# SCH.net
KiCad netlist of a schematic drawn in Altium Designer
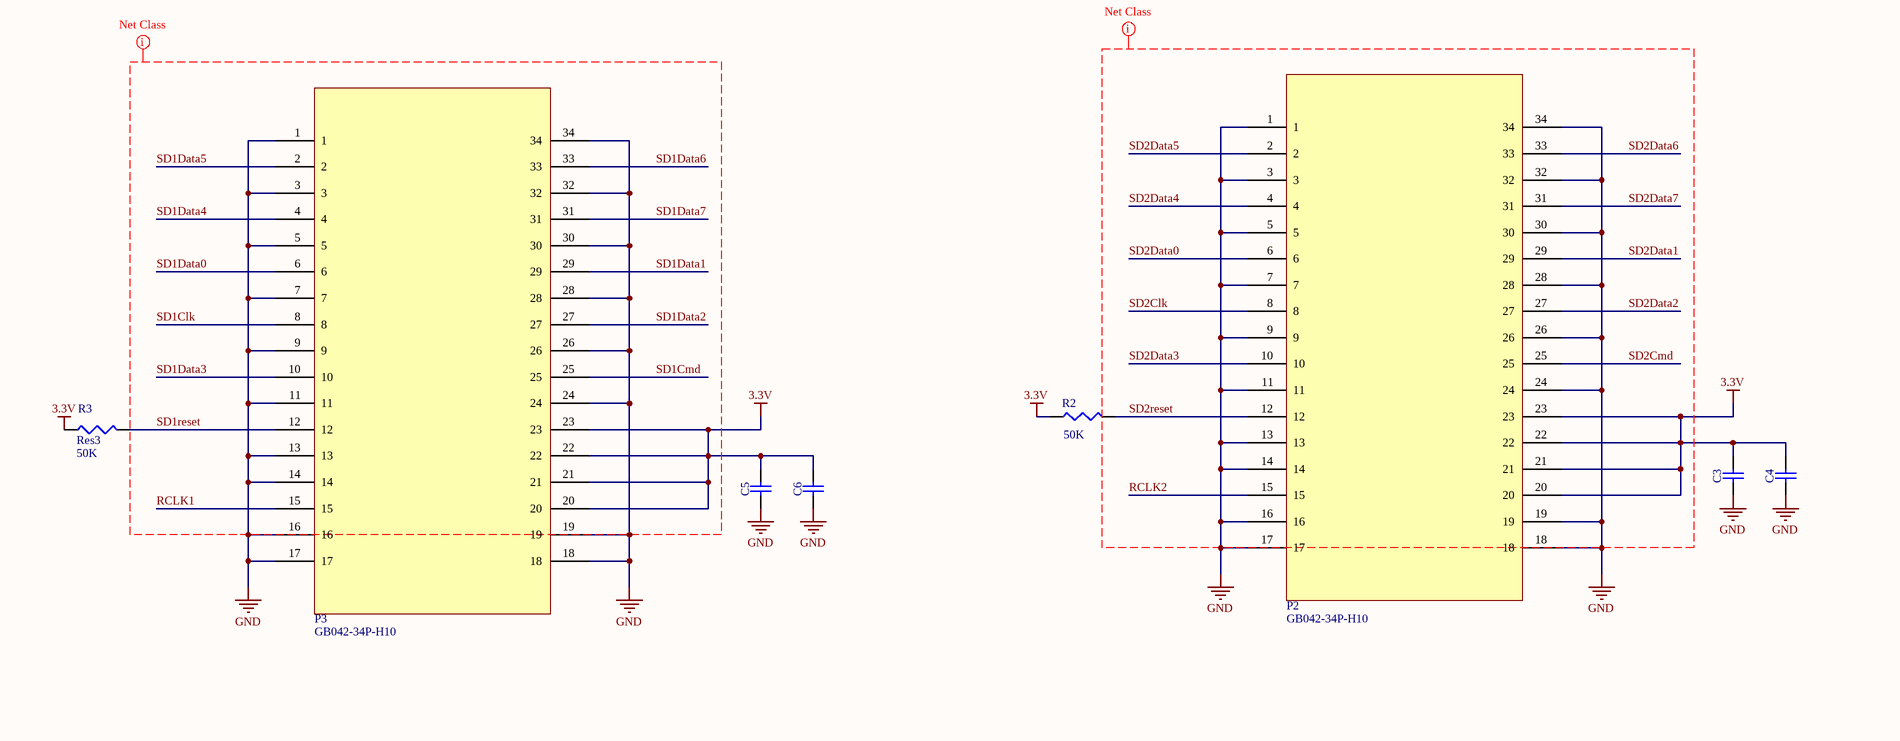
[diagram p0: SCH.SchDoc, top left]
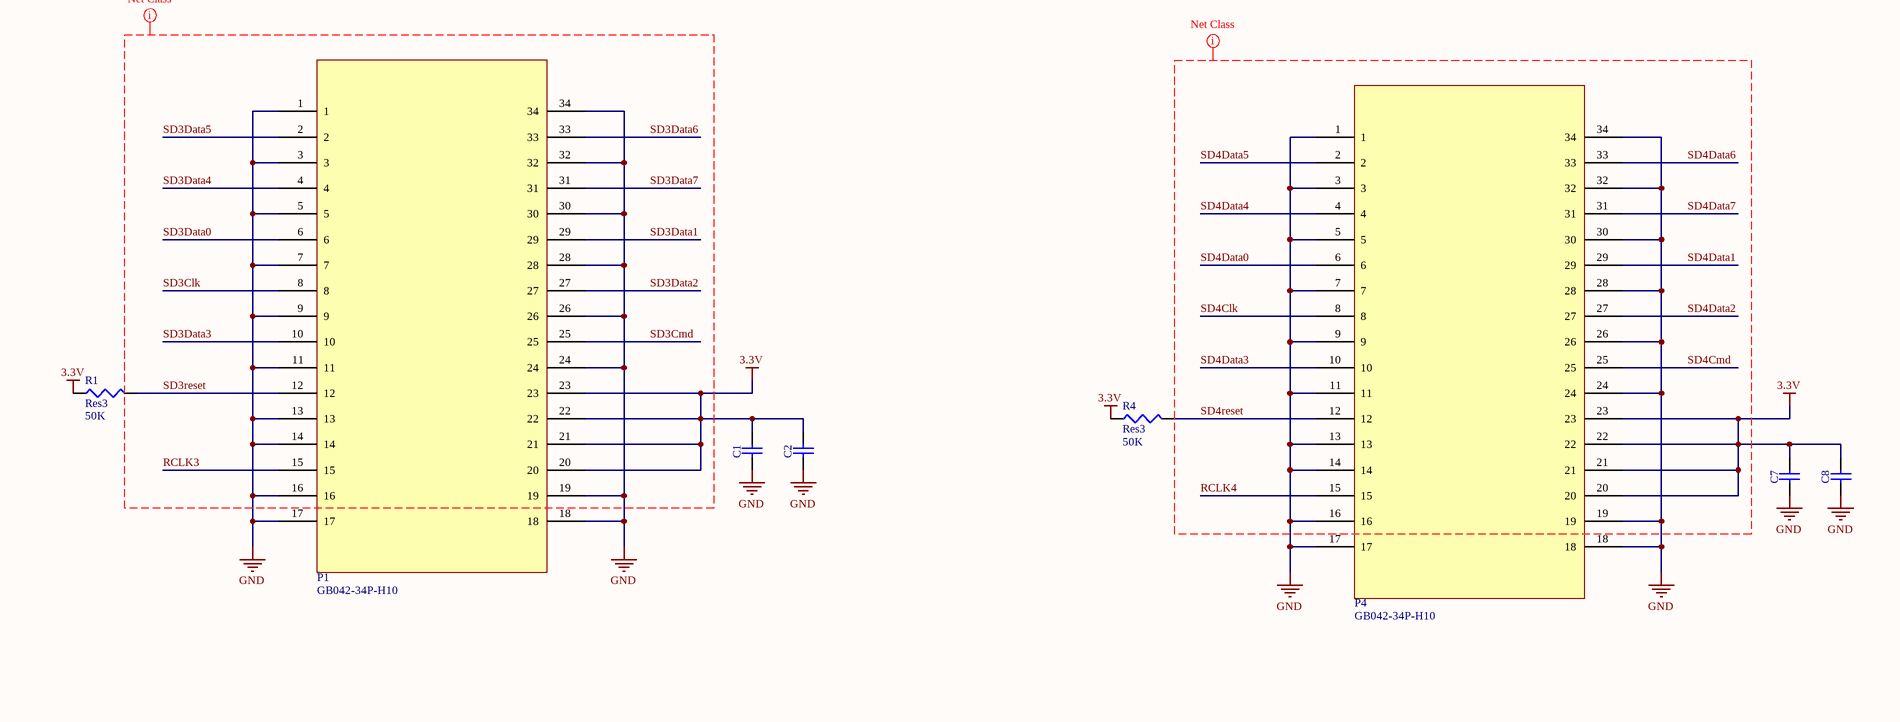
[diagram p1: SCH.SchDoc, top right]
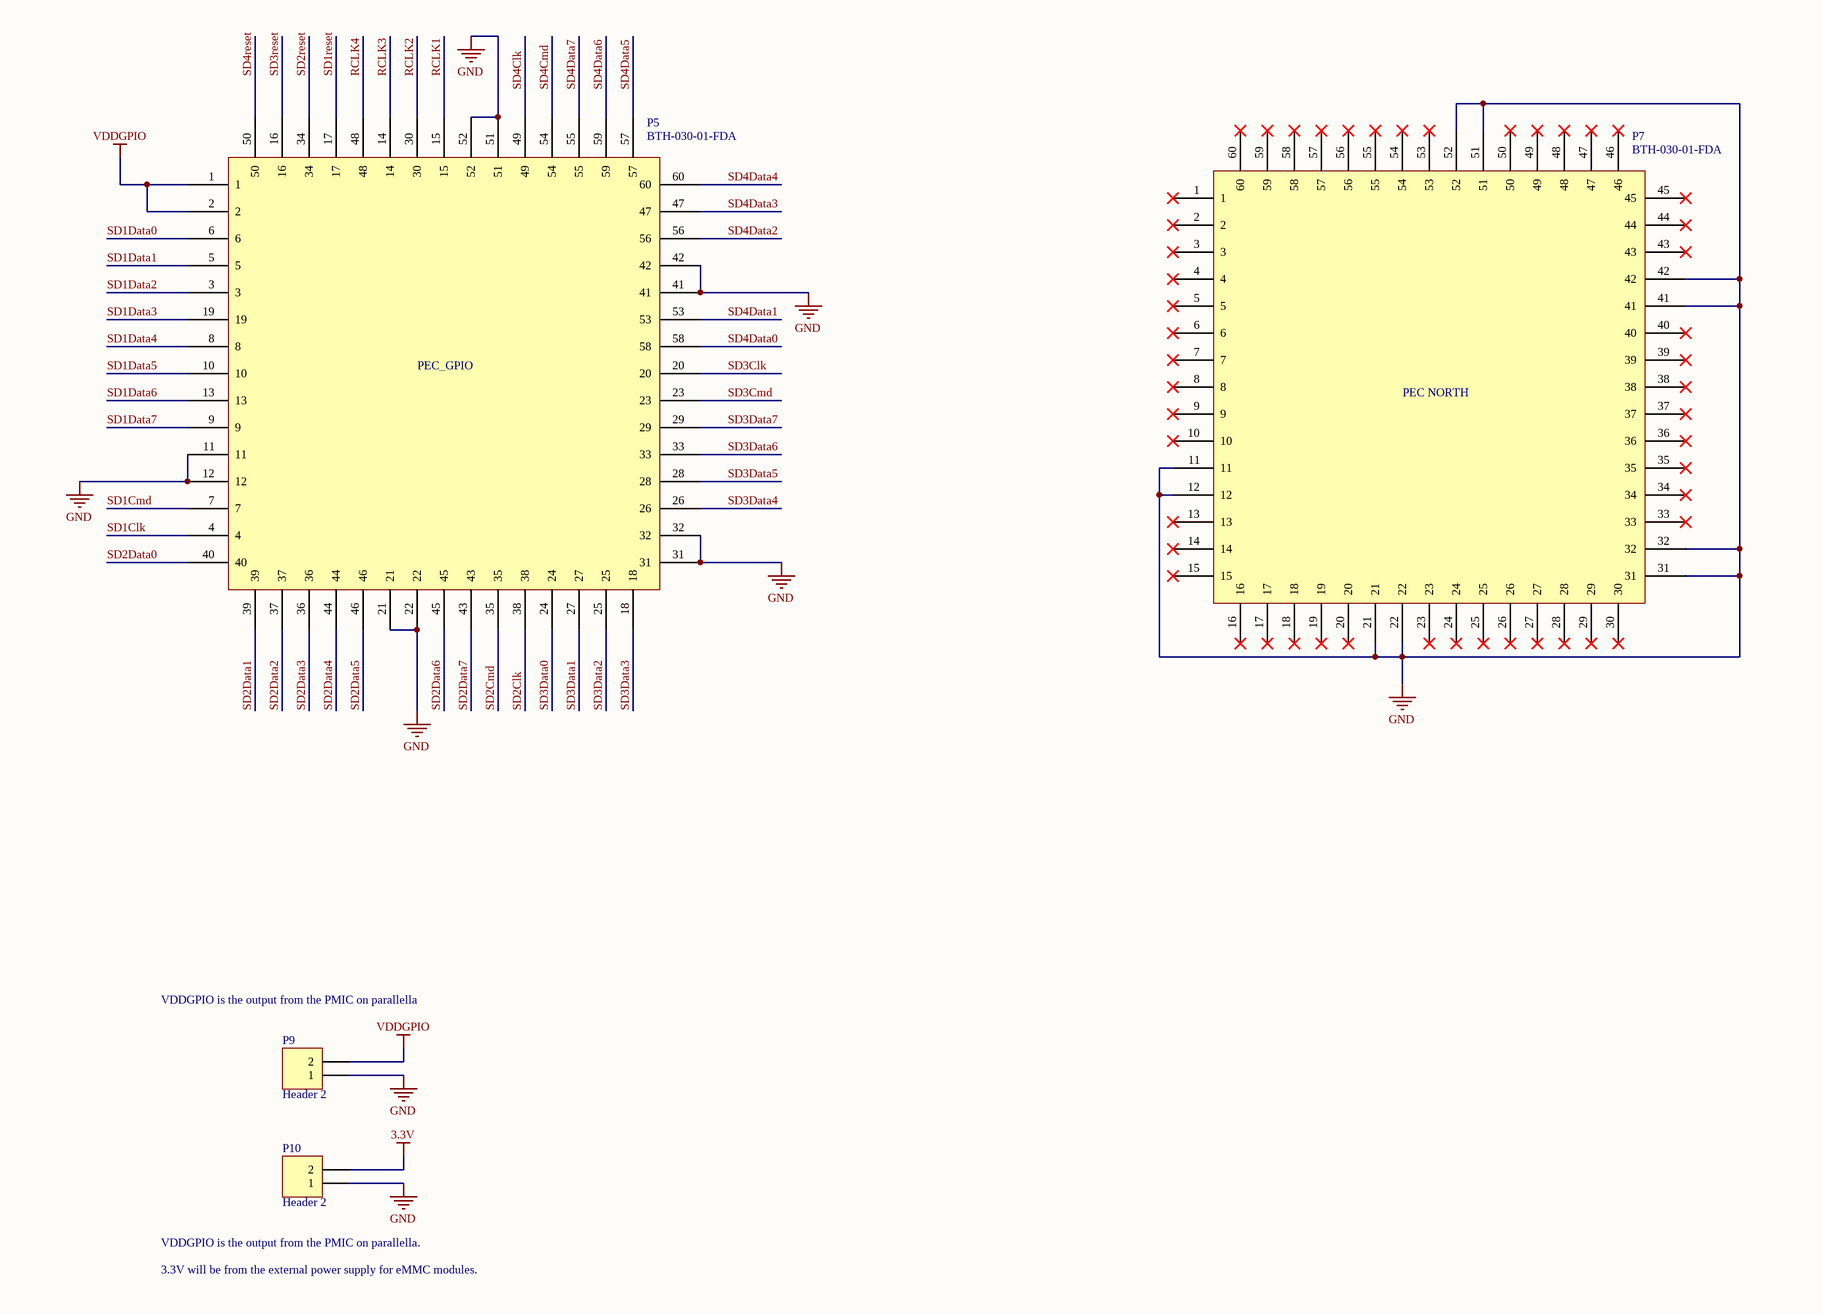
[diagram p2: SCH.SchDoc, bottom left]
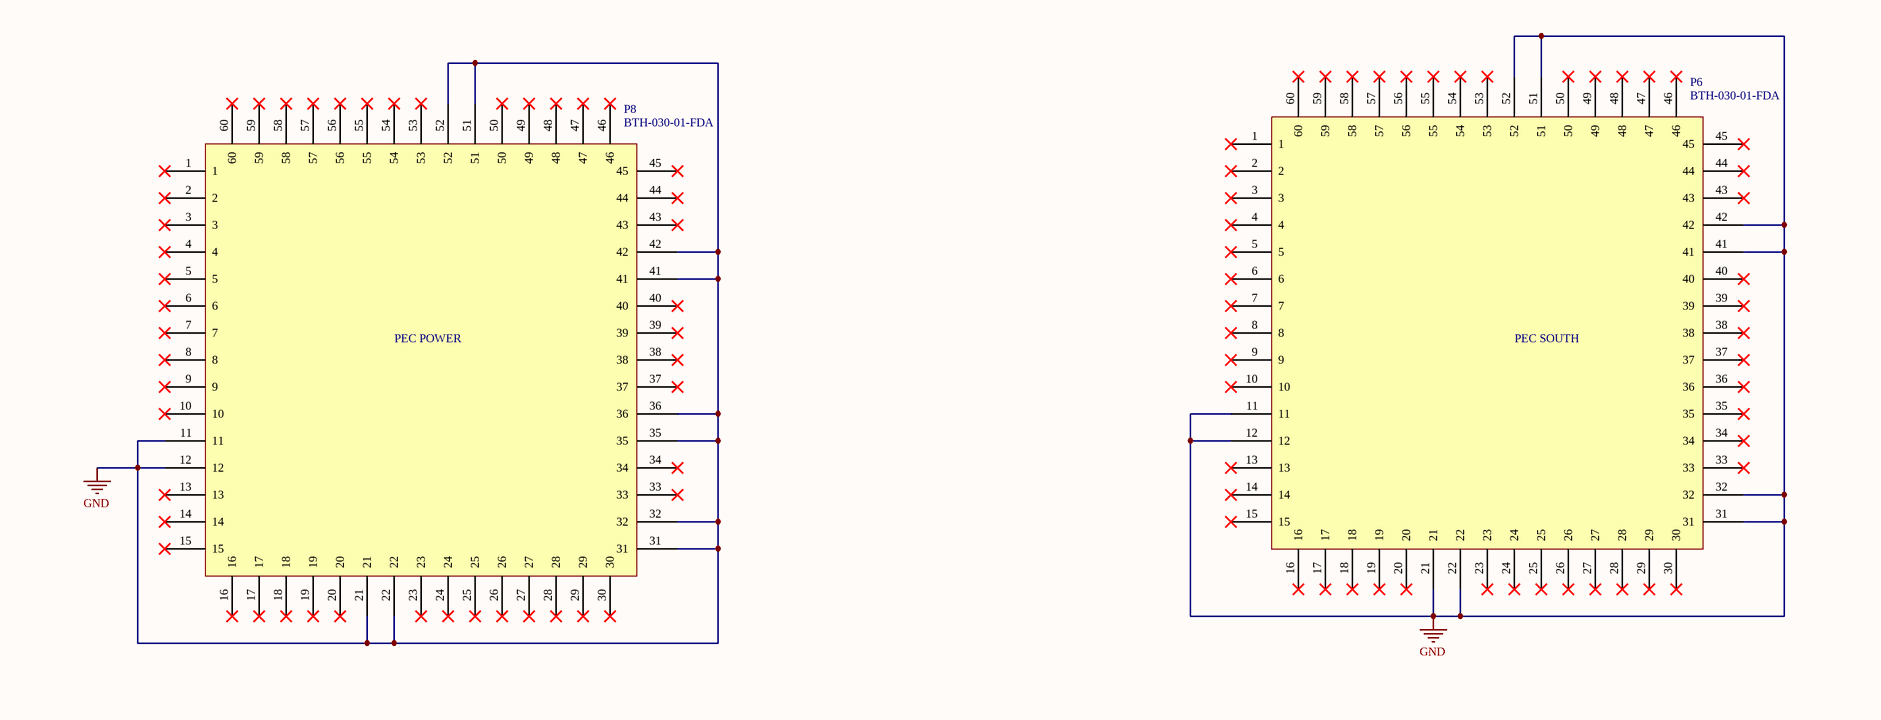
[diagram p3: SCH.SchDoc, bottom right]

(export (version "E")
  (design (tool "Eeschema 10.0.6"))
  (components
    (comp (ref "C1")
      (value "4.7uF")
      (footprint "CAPC3216X140N")
      (description "Non-polarised capacitor")
      (fields
        (field (name "PART NUMBER") "CC1206_4.7UF_16V_10%_X5R")
        (field (name "VOLTAGE") "16V")
        (field (name "AUTHOR") "CERN DEM JLC")
      )
      (libsource (lib "Capacitors") (part "Capacitor - non polarized"))
    )
    (comp (ref "C2")
      (value "100nF")
      (footprint "CAPC1608X87N")
      (description "Non-polarised capacitor")
      (fields
        (field (name "PART NUMBER") "CC0603_100NF_50V_10%_X7R")
        (field (name "VOLTAGE") "50V")
        (field (name "AUTHOR") "CERN DEM JLC")
      )
      (libsource (lib "Capacitors") (part "Capacitor - non polarized"))
    )
    (comp (ref "C3")
      (value "4.7uF")
      (footprint "CAPC3216X140N")
      (description "Non-polarised capacitor")
      (fields
        (field (name "PART NUMBER") "CC1206_4.7UF_16V_10%_X5R")
        (field (name "VOLTAGE") "16V")
        (field (name "AUTHOR") "CERN DEM JLC")
      )
      (libsource (lib "Capacitors") (part "Capacitor - non polarized"))
    )
    (comp (ref "C4")
      (value "100nF")
      (footprint "CAPC1608X87N")
      (description "Non-polarised capacitor")
      (fields
        (field (name "PART NUMBER") "CC0603_100NF_50V_10%_X7R")
        (field (name "VOLTAGE") "50V")
        (field (name "AUTHOR") "CERN DEM JLC")
      )
      (libsource (lib "Capacitors") (part "Capacitor - non polarized"))
    )
    (comp (ref "C5")
      (value "4.7uF")
      (footprint "CAPC3216X140N")
      (description "Non-polarised capacitor")
      (fields
        (field (name "PART NUMBER") "CC1206_4.7UF_16V_10%_X5R")
        (field (name "VOLTAGE") "16V")
        (field (name "AUTHOR") "CERN DEM JLC")
      )
      (libsource (lib "Capacitors") (part "Capacitor - non polarized"))
    )
    (comp (ref "C6")
      (value "100nF")
      (footprint "CAPC1608X87N")
      (description "Non-polarised capacitor")
      (fields
        (field (name "PART NUMBER") "CC0603_100NF_50V_10%_X7R")
        (field (name "VOLTAGE") "50V")
        (field (name "AUTHOR") "CERN DEM JLC")
      )
      (libsource (lib "Capacitors") (part "Capacitor - non polarized"))
    )
    (comp (ref "C7")
      (value "4.7uF")
      (footprint "CAPC3216X140N")
      (description "Non-polarised capacitor")
      (fields
        (field (name "PART NUMBER") "CC1206_4.7UF_16V_10%_X5R")
        (field (name "VOLTAGE") "16V")
        (field (name "AUTHOR") "CERN DEM JLC")
      )
      (libsource (lib "Capacitors") (part "Capacitor - non polarized"))
    )
    (comp (ref "C8")
      (value "100nF")
      (footprint "CAPC1608X87N")
      (description "Non-polarised capacitor")
      (fields
        (field (name "PART NUMBER") "CC0603_100NF_50V_10%_X7R")
        (field (name "VOLTAGE") "50V")
        (field (name "AUTHOR") "CERN DEM JLC")
      )
      (libsource (lib "Capacitors") (part "Capacitor - non polarized"))
    )
    (comp (ref "P1")
      (value "GB042-34P-H10")
      (footprint "GB042-34P-H10")
      (libsource (lib "Schlib1") (part "GB042-34P-H10"))
    )
    (comp (ref "P2")
      (value "GB042-34P-H10")
      (footprint "GB042-34P-H10")
      (libsource (lib "Schlib1") (part "GB042-34P-H10"))
    )
    (comp (ref "P3")
      (value "GB042-34P-H10")
      (footprint "GB042-34P-H10")
      (libsource (lib "Schlib1") (part "GB042-34P-H10"))
    )
    (comp (ref "P4")
      (value "GB042-34P-H10")
      (footprint "GB042-34P-H10")
      (libsource (lib "Schlib1") (part "GB042-34P-H10"))
    )
    (comp (ref "P5")
      (value "BTH-030-01-FDA")
      (footprint "BTH-030-01-F-D-A")
      (libsource (lib "") (part "BTH-030-01-FDA_1"))
    )
    (comp (ref "P6")
      (value "BTH-030-01-FDA")
      (footprint "BTH-030-01-F-D-A")
      (libsource (lib "Schlib1") (part "BTH-030-01-FDA"))
    )
    (comp (ref "P7")
      (value "BTH-030-01-FDA")
      (footprint "BTH-030-01-F-D-A")
      (libsource (lib "Schlib1") (part "BTH-030-01-FDA"))
    )
    (comp (ref "P8")
      (value "BTH-030-01-FDA")
      (footprint "BTH-030-01-F-D-A")
      (libsource (lib "Schlib1") (part "BTH-030-01-FDA"))
    )
    (comp (ref "P9")
      (value "Header 2")
      (footprint "HDR1X2")
      (description "Header, 2-Pin")
      (fields (field (name "PUBLISHER") "Altium Limited"))
      (libsource (lib "Miscellaneous Connectors") (part "Header 2"))
    )
    (comp (ref "P10")
      (value "Header 2")
      (footprint "HDR1X2")
      (description "Header, 2-Pin")
      (fields (field (name "PUBLISHER") "Altium Limited"))
      (libsource (lib "Miscellaneous Connectors") (part "Header 2"))
    )
    (comp (ref "R1")
      (value "Res3")
      (footprint "J1-0603")
      (description "Resistor")
      (fields (field (name "ALTIUM_VALUE") "50K") (field (name "PUBLISHER") "Altium Limited"))
      (libsource (lib "Miscellaneous Devices") (part "Res3"))
    )
    (comp (ref "R2")
      (value "50K")
      (footprint "J1-0603")
      (description "Resistor")
      (fields (field (name "Comment") "Res3") (field (name "PUBLISHER") "Altium Limited"))
      (libsource (lib "Miscellaneous Devices") (part "Res3"))
    )
    (comp (ref "R3")
      (value "Res3")
      (footprint "J1-0603")
      (description "Resistor")
      (fields (field (name "ALTIUM_VALUE") "50K") (field (name "PUBLISHER") "Altium Limited"))
      (libsource (lib "Miscellaneous Devices") (part "Res3"))
    )
    (comp (ref "R4")
      (value "Res3")
      (footprint "J1-0603")
      (description "Resistor")
      (fields (field (name "ALTIUM_VALUE") "50K") (field (name "PUBLISHER") "Altium Limited"))
      (libsource (lib "Miscellaneous Devices") (part "Res3"))
    )
  )
  (nets
    (net (code "1") (name "/RCLK1") (class "Default")
      (node (ref "P3") (pin "15") (pinfunction "15_15") (pintype "passive"))
      (node (ref "P5") (pin "15") (pinfunction "15_15") (pintype "passive"))
    )
    (net (code "2") (name "/RCLK2") (class "Default")
      (node (ref "P2") (pin "15") (pinfunction "15_15") (pintype "passive"))
      (node (ref "P5") (pin "30") (pinfunction "30_30") (pintype "passive"))
    )
    (net (code "3") (name "/RCLK3") (class "Default")
      (node (ref "P1") (pin "15") (pinfunction "15_15") (pintype "passive"))
      (node (ref "P5") (pin "14") (pinfunction "14_14") (pintype "passive"))
    )
    (net (code "4") (name "/RCLK4") (class "Default")
      (node (ref "P4") (pin "15") (pinfunction "15_15") (pintype "passive"))
      (node (ref "P5") (pin "48") (pinfunction "48_48") (pintype "passive"))
    )
    (net (code "5") (name "/SD1Clk") (class "Default")
      (node (ref "P3") (pin "8") (pinfunction "8_8") (pintype "passive"))
      (node (ref "P5") (pin "4") (pinfunction "4_4") (pintype "passive"))
    )
    (net (code "6") (name "/SD1Cmd") (class "Default")
      (node (ref "P3") (pin "25") (pinfunction "25_25") (pintype "passive"))
      (node (ref "P5") (pin "7") (pinfunction "7_7") (pintype "passive"))
    )
    (net (code "7") (name "/SD1Data0") (class "Default")
      (node (ref "P3") (pin "6") (pinfunction "6_6") (pintype "passive"))
      (node (ref "P5") (pin "6") (pinfunction "6_6") (pintype "passive"))
    )
    (net (code "8") (name "/SD1Data1") (class "Default")
      (node (ref "P3") (pin "29") (pinfunction "29_29") (pintype "passive"))
      (node (ref "P5") (pin "5") (pinfunction "5_5") (pintype "passive"))
    )
    (net (code "9") (name "/SD1Data2") (class "Default")
      (node (ref "P3") (pin "27") (pinfunction "27_27") (pintype "passive"))
      (node (ref "P5") (pin "3") (pinfunction "3_3") (pintype "passive"))
    )
    (net (code "10") (name "/SD1Data3") (class "Default")
      (node (ref "P3") (pin "10") (pinfunction "10_10") (pintype "passive"))
      (node (ref "P5") (pin "19") (pinfunction "19_19") (pintype "passive"))
    )
    (net (code "11") (name "/SD1Data4") (class "Default")
      (node (ref "P3") (pin "4") (pinfunction "4_4") (pintype "passive"))
      (node (ref "P5") (pin "8") (pinfunction "8_8") (pintype "passive"))
    )
    (net (code "12") (name "/SD1Data5") (class "Default")
      (node (ref "P3") (pin "2") (pinfunction "2_2") (pintype "passive"))
      (node (ref "P5") (pin "10") (pinfunction "10_10") (pintype "passive"))
    )
    (net (code "13") (name "/SD1Data6") (class "Default")
      (node (ref "P3") (pin "33") (pinfunction "33_33") (pintype "passive"))
      (node (ref "P5") (pin "13") (pinfunction "13_13") (pintype "passive"))
    )
    (net (code "14") (name "/SD1Data7") (class "Default")
      (node (ref "P3") (pin "31") (pinfunction "31_31") (pintype "passive"))
      (node (ref "P5") (pin "9") (pinfunction "9_9") (pintype "passive"))
    )
    (net (code "15") (name "/SD1reset") (class "Default")
      (node (ref "P3") (pin "12") (pinfunction "12_12") (pintype "passive"))
      (node (ref "P5") (pin "17") (pinfunction "17_17") (pintype "passive"))
      (node (ref "R3") (pin "2") (pinfunction "2_2") (pintype "passive"))
    )
    (net (code "16") (name "/SD2Clk") (class "Default")
      (node (ref "P2") (pin "8") (pinfunction "8_8") (pintype "passive"))
      (node (ref "P5") (pin "38") (pinfunction "38_38") (pintype "passive"))
    )
    (net (code "17") (name "/SD2Cmd") (class "Default")
      (node (ref "P2") (pin "25") (pinfunction "25_25") (pintype "passive"))
      (node (ref "P5") (pin "35") (pinfunction "35_35") (pintype "passive"))
    )
    (net (code "18") (name "/SD2Data0") (class "Default")
      (node (ref "P2") (pin "6") (pinfunction "6_6") (pintype "passive"))
      (node (ref "P5") (pin "40") (pinfunction "40_40") (pintype "passive"))
    )
    (net (code "19") (name "/SD2Data1") (class "Default")
      (node (ref "P2") (pin "29") (pinfunction "29_29") (pintype "passive"))
      (node (ref "P5") (pin "39") (pinfunction "39_39") (pintype "passive"))
    )
    (net (code "20") (name "/SD2Data2") (class "Default")
      (node (ref "P2") (pin "27") (pinfunction "27_27") (pintype "passive"))
      (node (ref "P5") (pin "37") (pinfunction "37_37") (pintype "passive"))
    )
    (net (code "21") (name "/SD2Data3") (class "Default")
      (node (ref "P2") (pin "10") (pinfunction "10_10") (pintype "passive"))
      (node (ref "P5") (pin "36") (pinfunction "36_36") (pintype "passive"))
    )
    (net (code "22") (name "/SD2Data4") (class "Default")
      (node (ref "P2") (pin "4") (pinfunction "4_4") (pintype "passive"))
      (node (ref "P5") (pin "44") (pinfunction "44_44") (pintype "passive"))
    )
    (net (code "23") (name "/SD2Data5") (class "Default")
      (node (ref "P2") (pin "2") (pinfunction "2_2") (pintype "passive"))
      (node (ref "P5") (pin "46") (pinfunction "46_46") (pintype "passive"))
    )
    (net (code "24") (name "/SD2Data6") (class "Default")
      (node (ref "P2") (pin "33") (pinfunction "33_33") (pintype "passive"))
      (node (ref "P5") (pin "45") (pinfunction "45_45") (pintype "passive"))
    )
    (net (code "25") (name "/SD2Data7") (class "Default")
      (node (ref "P2") (pin "31") (pinfunction "31_31") (pintype "passive"))
      (node (ref "P5") (pin "43") (pinfunction "43_43") (pintype "passive"))
    )
    (net (code "26") (name "/SD2reset") (class "Default")
      (node (ref "P2") (pin "12") (pinfunction "12_12") (pintype "passive"))
      (node (ref "P5") (pin "34") (pinfunction "34_34") (pintype "passive"))
      (node (ref "R2") (pin "2") (pinfunction "2_2") (pintype "passive"))
    )
    (net (code "27") (name "/SD3Clk") (class "Default")
      (node (ref "P1") (pin "8") (pinfunction "8_8") (pintype "passive"))
      (node (ref "P5") (pin "20") (pinfunction "20_20") (pintype "passive"))
    )
    (net (code "28") (name "/SD3Cmd") (class "Default")
      (node (ref "P1") (pin "25") (pinfunction "25_25") (pintype "passive"))
      (node (ref "P5") (pin "23") (pinfunction "23_23") (pintype "passive"))
    )
    (net (code "29") (name "/SD3Data0") (class "Default")
      (node (ref "P1") (pin "6") (pinfunction "6_6") (pintype "passive"))
      (node (ref "P5") (pin "24") (pinfunction "24_24") (pintype "passive"))
    )
    (net (code "30") (name "/SD3Data1") (class "Default")
      (node (ref "P1") (pin "29") (pinfunction "29_29") (pintype "passive"))
      (node (ref "P5") (pin "27") (pinfunction "27_27") (pintype "passive"))
    )
    (net (code "31") (name "/SD3Data2") (class "Default")
      (node (ref "P1") (pin "27") (pinfunction "27_27") (pintype "passive"))
      (node (ref "P5") (pin "25") (pinfunction "25_25") (pintype "passive"))
    )
    (net (code "32") (name "/SD3Data3") (class "Default")
      (node (ref "P1") (pin "10") (pinfunction "10_10") (pintype "passive"))
      (node (ref "P5") (pin "18") (pinfunction "18_18") (pintype "passive"))
    )
    (net (code "33") (name "/SD3Data4") (class "Default")
      (node (ref "P1") (pin "4") (pinfunction "4_4") (pintype "passive"))
      (node (ref "P5") (pin "26") (pinfunction "26_26") (pintype "passive"))
    )
    (net (code "34") (name "/SD3Data5") (class "Default")
      (node (ref "P1") (pin "2") (pinfunction "2_2") (pintype "passive"))
      (node (ref "P5") (pin "28") (pinfunction "28_28") (pintype "passive"))
    )
    (net (code "35") (name "/SD3Data6") (class "Default")
      (node (ref "P1") (pin "33") (pinfunction "33_33") (pintype "passive"))
      (node (ref "P5") (pin "33") (pinfunction "33_33") (pintype "passive"))
    )
    (net (code "36") (name "/SD3Data7") (class "Default")
      (node (ref "P1") (pin "31") (pinfunction "31_31") (pintype "passive"))
      (node (ref "P5") (pin "29") (pinfunction "29_29") (pintype "passive"))
    )
    (net (code "37") (name "/SD3reset") (class "Default")
      (node (ref "P1") (pin "12") (pinfunction "12_12") (pintype "passive"))
      (node (ref "P5") (pin "16") (pinfunction "16_16") (pintype "passive"))
      (node (ref "R1") (pin "2") (pinfunction "2_2") (pintype "passive"))
    )
    (net (code "38") (name "/SD4Clk") (class "Default")
      (node (ref "P4") (pin "8") (pinfunction "8_8") (pintype "passive"))
      (node (ref "P5") (pin "49") (pinfunction "49_49") (pintype "passive"))
    )
    (net (code "39") (name "/SD4Cmd") (class "Default")
      (node (ref "P4") (pin "25") (pinfunction "25_25") (pintype "passive"))
      (node (ref "P5") (pin "54") (pinfunction "54_54") (pintype "passive"))
    )
    (net (code "40") (name "/SD4Data0") (class "Default")
      (node (ref "P4") (pin "6") (pinfunction "6_6") (pintype "passive"))
      (node (ref "P5") (pin "58") (pinfunction "58_58") (pintype "passive"))
    )
    (net (code "41") (name "/SD4Data1") (class "Default")
      (node (ref "P4") (pin "29") (pinfunction "29_29") (pintype "passive"))
      (node (ref "P5") (pin "53") (pinfunction "53_53") (pintype "passive"))
    )
    (net (code "42") (name "/SD4Data2") (class "Default")
      (node (ref "P4") (pin "27") (pinfunction "27_27") (pintype "passive"))
      (node (ref "P5") (pin "56") (pinfunction "56_56") (pintype "passive"))
    )
    (net (code "43") (name "/SD4Data3") (class "Default")
      (node (ref "P4") (pin "10") (pinfunction "10_10") (pintype "passive"))
      (node (ref "P5") (pin "47") (pinfunction "47_47") (pintype "passive"))
    )
    (net (code "44") (name "/SD4Data4") (class "Default")
      (node (ref "P4") (pin "4") (pinfunction "4_4") (pintype "passive"))
      (node (ref "P5") (pin "60") (pinfunction "60_60") (pintype "passive"))
    )
    (net (code "45") (name "/SD4Data5") (class "Default")
      (node (ref "P4") (pin "2") (pinfunction "2_2") (pintype "passive"))
      (node (ref "P5") (pin "57") (pinfunction "57_57") (pintype "passive"))
    )
    (net (code "46") (name "/SD4Data6") (class "Default")
      (node (ref "P4") (pin "33") (pinfunction "33_33") (pintype "passive"))
      (node (ref "P5") (pin "59") (pinfunction "59_59") (pintype "passive"))
    )
    (net (code "47") (name "/SD4Data7") (class "Default")
      (node (ref "P4") (pin "31") (pinfunction "31_31") (pintype "passive"))
      (node (ref "P5") (pin "55") (pinfunction "55_55") (pintype "passive"))
    )
    (net (code "48") (name "/SD4reset") (class "Default")
      (node (ref "P4") (pin "12") (pinfunction "12_12") (pintype "passive"))
      (node (ref "P5") (pin "50") (pinfunction "50_50") (pintype "passive"))
      (node (ref "R4") (pin "2") (pinfunction "2_2") (pintype "passive"))
    )
    (net (code "49") (name "3.3V") (class "Default")
      (node (ref "C1") (pin "2") (pinfunction "2_2") (pintype "passive"))
      (node (ref "C2") (pin "2") (pinfunction "2_2") (pintype "passive"))
      (node (ref "C3") (pin "2") (pinfunction "2_2") (pintype "passive"))
      (node (ref "C4") (pin "2") (pinfunction "2_2") (pintype "passive"))
      (node (ref "C5") (pin "2") (pinfunction "2_2") (pintype "passive"))
      (node (ref "C6") (pin "2") (pinfunction "2_2") (pintype "passive"))
      (node (ref "C7") (pin "2") (pinfunction "2_2") (pintype "passive"))
      (node (ref "C8") (pin "2") (pinfunction "2_2") (pintype "passive"))
      (node (ref "P1") (pin "20") (pinfunction "20_20") (pintype "passive"))
      (node (ref "P1") (pin "21") (pinfunction "21_21") (pintype "passive"))
      (node (ref "P1") (pin "22") (pinfunction "22_22") (pintype "passive"))
      (node (ref "P1") (pin "23") (pinfunction "23_23") (pintype "passive"))
      (node (ref "P10") (pin "2") (pinfunction "2_2") (pintype "passive"))
      (node (ref "P2") (pin "20") (pinfunction "20_20") (pintype "passive"))
      (node (ref "P2") (pin "21") (pinfunction "21_21") (pintype "passive"))
      (node (ref "P2") (pin "22") (pinfunction "22_22") (pintype "passive"))
      (node (ref "P2") (pin "23") (pinfunction "23_23") (pintype "passive"))
      (node (ref "P3") (pin "20") (pinfunction "20_20") (pintype "passive"))
      (node (ref "P3") (pin "21") (pinfunction "21_21") (pintype "passive"))
      (node (ref "P3") (pin "22") (pinfunction "22_22") (pintype "passive"))
      (node (ref "P3") (pin "23") (pinfunction "23_23") (pintype "passive"))
      (node (ref "P4") (pin "20") (pinfunction "20_20") (pintype "passive"))
      (node (ref "P4") (pin "21") (pinfunction "21_21") (pintype "passive"))
      (node (ref "P4") (pin "22") (pinfunction "22_22") (pintype "passive"))
      (node (ref "P4") (pin "23") (pinfunction "23_23") (pintype "passive"))
      (node (ref "R1") (pin "1") (pinfunction "1_1") (pintype "passive"))
      (node (ref "R2") (pin "1") (pinfunction "1_1") (pintype "passive"))
      (node (ref "R3") (pin "1") (pinfunction "1_1") (pintype "passive"))
      (node (ref "R4") (pin "1") (pinfunction "1_1") (pintype "passive"))
    )
    (net (code "50") (name "GND") (class "Default")
      (node (ref "C1") (pin "1") (pinfunction "1_1") (pintype "passive"))
      (node (ref "C2") (pin "1") (pinfunction "1_1") (pintype "passive"))
      (node (ref "C3") (pin "1") (pinfunction "1_1") (pintype "passive"))
      (node (ref "C4") (pin "1") (pinfunction "1_1") (pintype "passive"))
      (node (ref "C5") (pin "1") (pinfunction "1_1") (pintype "passive"))
      (node (ref "C6") (pin "1") (pinfunction "1_1") (pintype "passive"))
      (node (ref "C7") (pin "1") (pinfunction "1_1") (pintype "passive"))
      (node (ref "C8") (pin "1") (pinfunction "1_1") (pintype "passive"))
      (node (ref "P1") (pin "1") (pinfunction "1_1") (pintype "passive"))
      (node (ref "P1") (pin "11") (pinfunction "11_11") (pintype "passive"))
      (node (ref "P1") (pin "13") (pinfunction "13_13") (pintype "passive"))
      (node (ref "P1") (pin "14") (pinfunction "14_14") (pintype "passive"))
      (node (ref "P1") (pin "16") (pinfunction "16_16") (pintype "passive"))
      (node (ref "P1") (pin "17") (pinfunction "17_17") (pintype "passive"))
      (node (ref "P1") (pin "18") (pinfunction "18_18") (pintype "passive"))
      (node (ref "P1") (pin "19") (pinfunction "19_19") (pintype "passive"))
      (node (ref "P1") (pin "24") (pinfunction "24_24") (pintype "passive"))
      (node (ref "P1") (pin "26") (pinfunction "26_26") (pintype "passive"))
      (node (ref "P1") (pin "28") (pinfunction "28_28") (pintype "passive"))
      (node (ref "P1") (pin "3") (pinfunction "3_3") (pintype "passive"))
      (node (ref "P1") (pin "30") (pinfunction "30_30") (pintype "passive"))
      (node (ref "P1") (pin "32") (pinfunction "32_32") (pintype "passive"))
      (node (ref "P1") (pin "34") (pinfunction "34_34") (pintype "passive"))
      (node (ref "P1") (pin "5") (pinfunction "5_5") (pintype "passive"))
      (node (ref "P1") (pin "7") (pinfunction "7_7") (pintype "passive"))
      (node (ref "P1") (pin "9") (pinfunction "9_9") (pintype "passive"))
      (node (ref "P10") (pin "1") (pinfunction "1_1") (pintype "passive"))
      (node (ref "P2") (pin "1") (pinfunction "1_1") (pintype "passive"))
      (node (ref "P2") (pin "11") (pinfunction "11_11") (pintype "passive"))
      (node (ref "P2") (pin "13") (pinfunction "13_13") (pintype "passive"))
      (node (ref "P2") (pin "14") (pinfunction "14_14") (pintype "passive"))
      (node (ref "P2") (pin "16") (pinfunction "16_16") (pintype "passive"))
      (node (ref "P2") (pin "17") (pinfunction "17_17") (pintype "passive"))
      (node (ref "P2") (pin "18") (pinfunction "18_18") (pintype "passive"))
      (node (ref "P2") (pin "19") (pinfunction "19_19") (pintype "passive"))
      (node (ref "P2") (pin "24") (pinfunction "24_24") (pintype "passive"))
      (node (ref "P2") (pin "26") (pinfunction "26_26") (pintype "passive"))
      (node (ref "P2") (pin "28") (pinfunction "28_28") (pintype "passive"))
      (node (ref "P2") (pin "3") (pinfunction "3_3") (pintype "passive"))
      (node (ref "P2") (pin "30") (pinfunction "30_30") (pintype "passive"))
      (node (ref "P2") (pin "32") (pinfunction "32_32") (pintype "passive"))
      (node (ref "P2") (pin "34") (pinfunction "34_34") (pintype "passive"))
      (node (ref "P2") (pin "5") (pinfunction "5_5") (pintype "passive"))
      (node (ref "P2") (pin "7") (pinfunction "7_7") (pintype "passive"))
      (node (ref "P2") (pin "9") (pinfunction "9_9") (pintype "passive"))
      (node (ref "P3") (pin "1") (pinfunction "1_1") (pintype "passive"))
      (node (ref "P3") (pin "11") (pinfunction "11_11") (pintype "passive"))
      (node (ref "P3") (pin "13") (pinfunction "13_13") (pintype "passive"))
      (node (ref "P3") (pin "14") (pinfunction "14_14") (pintype "passive"))
      (node (ref "P3") (pin "16") (pinfunction "16_16") (pintype "passive"))
      (node (ref "P3") (pin "17") (pinfunction "17_17") (pintype "passive"))
      (node (ref "P3") (pin "18") (pinfunction "18_18") (pintype "passive"))
      (node (ref "P3") (pin "19") (pinfunction "19_19") (pintype "passive"))
      (node (ref "P3") (pin "24") (pinfunction "24_24") (pintype "passive"))
      (node (ref "P3") (pin "26") (pinfunction "26_26") (pintype "passive"))
      (node (ref "P3") (pin "28") (pinfunction "28_28") (pintype "passive"))
      (node (ref "P3") (pin "3") (pinfunction "3_3") (pintype "passive"))
      (node (ref "P3") (pin "30") (pinfunction "30_30") (pintype "passive"))
      (node (ref "P3") (pin "32") (pinfunction "32_32") (pintype "passive"))
      (node (ref "P3") (pin "34") (pinfunction "34_34") (pintype "passive"))
      (node (ref "P3") (pin "5") (pinfunction "5_5") (pintype "passive"))
      (node (ref "P3") (pin "7") (pinfunction "7_7") (pintype "passive"))
      (node (ref "P3") (pin "9") (pinfunction "9_9") (pintype "passive"))
      (node (ref "P4") (pin "1") (pinfunction "1_1") (pintype "passive"))
      (node (ref "P4") (pin "11") (pinfunction "11_11") (pintype "passive"))
      (node (ref "P4") (pin "13") (pinfunction "13_13") (pintype "passive"))
      (node (ref "P4") (pin "14") (pinfunction "14_14") (pintype "passive"))
      (node (ref "P4") (pin "16") (pinfunction "16_16") (pintype "passive"))
      (node (ref "P4") (pin "17") (pinfunction "17_17") (pintype "passive"))
      (node (ref "P4") (pin "18") (pinfunction "18_18") (pintype "passive"))
      (node (ref "P4") (pin "19") (pinfunction "19_19") (pintype "passive"))
      (node (ref "P4") (pin "24") (pinfunction "24_24") (pintype "passive"))
      (node (ref "P4") (pin "26") (pinfunction "26_26") (pintype "passive"))
      (node (ref "P4") (pin "28") (pinfunction "28_28") (pintype "passive"))
      (node (ref "P4") (pin "3") (pinfunction "3_3") (pintype "passive"))
      (node (ref "P4") (pin "30") (pinfunction "30_30") (pintype "passive"))
      (node (ref "P4") (pin "32") (pinfunction "32_32") (pintype "passive"))
      (node (ref "P4") (pin "34") (pinfunction "34_34") (pintype "passive"))
      (node (ref "P4") (pin "5") (pinfunction "5_5") (pintype "passive"))
      (node (ref "P4") (pin "7") (pinfunction "7_7") (pintype "passive"))
      (node (ref "P4") (pin "9") (pinfunction "9_9") (pintype "passive"))
      (node (ref "P5") (pin "11") (pinfunction "11_11") (pintype "passive"))
      (node (ref "P5") (pin "12") (pinfunction "12_12") (pintype "passive"))
      (node (ref "P5") (pin "21") (pinfunction "21_21") (pintype "passive"))
      (node (ref "P5") (pin "22") (pinfunction "22_22") (pintype "passive"))
      (node (ref "P5") (pin "31") (pinfunction "31_31") (pintype "passive"))
      (node (ref "P5") (pin "32") (pinfunction "32_32") (pintype "passive"))
      (node (ref "P5") (pin "41") (pinfunction "41_41") (pintype "passive"))
      (node (ref "P5") (pin "42") (pinfunction "42_42") (pintype "passive"))
      (node (ref "P5") (pin "51") (pinfunction "51_51") (pintype "passive"))
      (node (ref "P5") (pin "52") (pinfunction "52_52") (pintype "passive"))
      (node (ref "P6") (pin "11") (pinfunction "11_11") (pintype "passive"))
      (node (ref "P6") (pin "12") (pinfunction "12_12") (pintype "passive"))
      (node (ref "P6") (pin "21") (pinfunction "21_21") (pintype "passive"))
      (node (ref "P6") (pin "22") (pinfunction "22_22") (pintype "passive"))
      (node (ref "P6") (pin "31") (pinfunction "31_31") (pintype "passive"))
      (node (ref "P6") (pin "32") (pinfunction "32_32") (pintype "passive"))
      (node (ref "P6") (pin "41") (pinfunction "41_41") (pintype "passive"))
      (node (ref "P6") (pin "42") (pinfunction "42_42") (pintype "passive"))
      (node (ref "P6") (pin "51") (pinfunction "51_51") (pintype "passive"))
      (node (ref "P6") (pin "52") (pinfunction "52_52") (pintype "passive"))
      (node (ref "P7") (pin "11") (pinfunction "11_11") (pintype "passive"))
      (node (ref "P7") (pin "12") (pinfunction "12_12") (pintype "passive"))
      (node (ref "P7") (pin "21") (pinfunction "21_21") (pintype "passive"))
      (node (ref "P7") (pin "22") (pinfunction "22_22") (pintype "passive"))
      (node (ref "P7") (pin "31") (pinfunction "31_31") (pintype "passive"))
      (node (ref "P7") (pin "32") (pinfunction "32_32") (pintype "passive"))
      (node (ref "P7") (pin "41") (pinfunction "41_41") (pintype "passive"))
      (node (ref "P7") (pin "42") (pinfunction "42_42") (pintype "passive"))
      (node (ref "P7") (pin "51") (pinfunction "51_51") (pintype "passive"))
      (node (ref "P7") (pin "52") (pinfunction "52_52") (pintype "passive"))
      (node (ref "P8") (pin "11") (pinfunction "11_11") (pintype "passive"))
      (node (ref "P8") (pin "12") (pinfunction "12_12") (pintype "passive"))
      (node (ref "P8") (pin "21") (pinfunction "21_21") (pintype "passive"))
      (node (ref "P8") (pin "22") (pinfunction "22_22") (pintype "passive"))
      (node (ref "P8") (pin "31") (pinfunction "31_31") (pintype "passive"))
      (node (ref "P8") (pin "32") (pinfunction "32_32") (pintype "passive"))
      (node (ref "P8") (pin "35") (pinfunction "35_35") (pintype "passive"))
      (node (ref "P8") (pin "36") (pinfunction "36_36") (pintype "passive"))
      (node (ref "P8") (pin "41") (pinfunction "41_41") (pintype "passive"))
      (node (ref "P8") (pin "42") (pinfunction "42_42") (pintype "passive"))
      (node (ref "P8") (pin "51") (pinfunction "51_51") (pintype "passive"))
      (node (ref "P8") (pin "52") (pinfunction "52_52") (pintype "passive"))
      (node (ref "P9") (pin "1") (pinfunction "1_1") (pintype "passive"))
    )
    (net (code "51") (name "VDDGPIO") (class "Default")
      (node (ref "P5") (pin "1") (pinfunction "1_1") (pintype "passive"))
      (node (ref "P5") (pin "2") (pinfunction "2_2") (pintype "passive"))
      (node (ref "P9") (pin "2") (pinfunction "2_2") (pintype "passive"))
    )
    (net (code "52") (name "unconnected-(P6-Pad1)") (class "Default")
      (node (ref "P6") (pin "1") (pinfunction "1_1") (pintype "passive+no_connect"))
    )
    (net (code "53") (name "unconnected-(P6-Pad2)") (class "Default")
      (node (ref "P6") (pin "2") (pinfunction "2_2") (pintype "passive+no_connect"))
    )
    (net (code "54") (name "unconnected-(P6-Pad3)") (class "Default")
      (node (ref "P6") (pin "3") (pinfunction "3_3") (pintype "passive+no_connect"))
    )
    (net (code "55") (name "unconnected-(P6-Pad4)") (class "Default")
      (node (ref "P6") (pin "4") (pinfunction "4_4") (pintype "passive+no_connect"))
    )
    (net (code "56") (name "unconnected-(P6-Pad5)") (class "Default")
      (node (ref "P6") (pin "5") (pinfunction "5_5") (pintype "passive+no_connect"))
    )
    (net (code "57") (name "unconnected-(P6-Pad6)") (class "Default")
      (node (ref "P6") (pin "6") (pinfunction "6_6") (pintype "passive+no_connect"))
    )
    (net (code "58") (name "unconnected-(P6-Pad7)") (class "Default")
      (node (ref "P6") (pin "7") (pinfunction "7_7") (pintype "passive+no_connect"))
    )
    (net (code "59") (name "unconnected-(P6-Pad8)") (class "Default")
      (node (ref "P6") (pin "8") (pinfunction "8_8") (pintype "passive+no_connect"))
    )
    (net (code "60") (name "unconnected-(P6-Pad9)") (class "Default")
      (node (ref "P6") (pin "9") (pinfunction "9_9") (pintype "passive+no_connect"))
    )
    (net (code "61") (name "unconnected-(P6-Pad10)") (class "Default")
      (node (ref "P6") (pin "10") (pinfunction "10_10") (pintype "passive+no_connect"))
    )
    (net (code "62") (name "unconnected-(P6-Pad13)") (class "Default")
      (node (ref "P6") (pin "13") (pinfunction "13_13") (pintype "passive+no_connect"))
    )
    (net (code "63") (name "unconnected-(P6-Pad14)") (class "Default")
      (node (ref "P6") (pin "14") (pinfunction "14_14") (pintype "passive+no_connect"))
    )
    (net (code "64") (name "unconnected-(P6-Pad15)") (class "Default")
      (node (ref "P6") (pin "15") (pinfunction "15_15") (pintype "passive+no_connect"))
    )
    (net (code "65") (name "unconnected-(P6-Pad16)") (class "Default")
      (node (ref "P6") (pin "16") (pinfunction "16_16") (pintype "passive+no_connect"))
    )
    (net (code "66") (name "unconnected-(P6-Pad17)") (class "Default")
      (node (ref "P6") (pin "17") (pinfunction "17_17") (pintype "passive+no_connect"))
    )
    (net (code "67") (name "unconnected-(P6-Pad18)") (class "Default")
      (node (ref "P6") (pin "18") (pinfunction "18_18") (pintype "passive+no_connect"))
    )
    (net (code "68") (name "unconnected-(P6-Pad19)") (class "Default")
      (node (ref "P6") (pin "19") (pinfunction "19_19") (pintype "passive+no_connect"))
    )
    (net (code "69") (name "unconnected-(P6-Pad20)") (class "Default")
      (node (ref "P6") (pin "20") (pinfunction "20_20") (pintype "passive+no_connect"))
    )
    (net (code "70") (name "unconnected-(P6-Pad23)") (class "Default")
      (node (ref "P6") (pin "23") (pinfunction "23_23") (pintype "passive+no_connect"))
    )
    (net (code "71") (name "unconnected-(P6-Pad24)") (class "Default")
      (node (ref "P6") (pin "24") (pinfunction "24_24") (pintype "passive+no_connect"))
    )
    (net (code "72") (name "unconnected-(P6-Pad25)") (class "Default")
      (node (ref "P6") (pin "25") (pinfunction "25_25") (pintype "passive+no_connect"))
    )
    (net (code "73") (name "unconnected-(P6-Pad26)") (class "Default")
      (node (ref "P6") (pin "26") (pinfunction "26_26") (pintype "passive+no_connect"))
    )
    (net (code "74") (name "unconnected-(P6-Pad27)") (class "Default")
      (node (ref "P6") (pin "27") (pinfunction "27_27") (pintype "passive+no_connect"))
    )
    (net (code "75") (name "unconnected-(P6-Pad28)") (class "Default")
      (node (ref "P6") (pin "28") (pinfunction "28_28") (pintype "passive+no_connect"))
    )
    (net (code "76") (name "unconnected-(P6-Pad29)") (class "Default")
      (node (ref "P6") (pin "29") (pinfunction "29_29") (pintype "passive+no_connect"))
    )
    (net (code "77") (name "unconnected-(P6-Pad30)") (class "Default")
      (node (ref "P6") (pin "30") (pinfunction "30_30") (pintype "passive+no_connect"))
    )
    (net (code "78") (name "unconnected-(P6-Pad33)") (class "Default")
      (node (ref "P6") (pin "33") (pinfunction "33_33") (pintype "passive+no_connect"))
    )
    (net (code "79") (name "unconnected-(P6-Pad34)") (class "Default")
      (node (ref "P6") (pin "34") (pinfunction "34_34") (pintype "passive+no_connect"))
    )
    (net (code "80") (name "unconnected-(P6-Pad35)") (class "Default")
      (node (ref "P6") (pin "35") (pinfunction "35_35") (pintype "passive+no_connect"))
    )
    (net (code "81") (name "unconnected-(P6-Pad36)") (class "Default")
      (node (ref "P6") (pin "36") (pinfunction "36_36") (pintype "passive+no_connect"))
    )
    (net (code "82") (name "unconnected-(P6-Pad37)") (class "Default")
      (node (ref "P6") (pin "37") (pinfunction "37_37") (pintype "passive+no_connect"))
    )
    (net (code "83") (name "unconnected-(P6-Pad38)") (class "Default")
      (node (ref "P6") (pin "38") (pinfunction "38_38") (pintype "passive+no_connect"))
    )
    (net (code "84") (name "unconnected-(P6-Pad39)") (class "Default")
      (node (ref "P6") (pin "39") (pinfunction "39_39") (pintype "passive+no_connect"))
    )
    (net (code "85") (name "unconnected-(P6-Pad40)") (class "Default")
      (node (ref "P6") (pin "40") (pinfunction "40_40") (pintype "passive+no_connect"))
    )
    (net (code "86") (name "unconnected-(P6-Pad43)") (class "Default")
      (node (ref "P6") (pin "43") (pinfunction "43_43") (pintype "passive+no_connect"))
    )
    (net (code "87") (name "unconnected-(P6-Pad44)") (class "Default")
      (node (ref "P6") (pin "44") (pinfunction "44_44") (pintype "passive+no_connect"))
    )
    (net (code "88") (name "unconnected-(P6-Pad45)") (class "Default")
      (node (ref "P6") (pin "45") (pinfunction "45_45") (pintype "passive+no_connect"))
    )
    (net (code "89") (name "unconnected-(P6-Pad46)") (class "Default")
      (node (ref "P6") (pin "46") (pinfunction "46_46") (pintype "passive+no_connect"))
    )
    (net (code "90") (name "unconnected-(P6-Pad47)") (class "Default")
      (node (ref "P6") (pin "47") (pinfunction "47_47") (pintype "passive+no_connect"))
    )
    (net (code "91") (name "unconnected-(P6-Pad48)") (class "Default")
      (node (ref "P6") (pin "48") (pinfunction "48_48") (pintype "passive+no_connect"))
    )
    (net (code "92") (name "unconnected-(P6-Pad49)") (class "Default")
      (node (ref "P6") (pin "49") (pinfunction "49_49") (pintype "passive+no_connect"))
    )
    (net (code "93") (name "unconnected-(P6-Pad50)") (class "Default")
      (node (ref "P6") (pin "50") (pinfunction "50_50") (pintype "passive+no_connect"))
    )
    (net (code "94") (name "unconnected-(P6-Pad53)") (class "Default")
      (node (ref "P6") (pin "53") (pinfunction "53_53") (pintype "passive+no_connect"))
    )
    (net (code "95") (name "unconnected-(P6-Pad54)") (class "Default")
      (node (ref "P6") (pin "54") (pinfunction "54_54") (pintype "passive+no_connect"))
    )
    (net (code "96") (name "unconnected-(P6-Pad55)") (class "Default")
      (node (ref "P6") (pin "55") (pinfunction "55_55") (pintype "passive+no_connect"))
    )
    (net (code "97") (name "unconnected-(P6-Pad56)") (class "Default")
      (node (ref "P6") (pin "56") (pinfunction "56_56") (pintype "passive+no_connect"))
    )
    (net (code "98") (name "unconnected-(P6-Pad57)") (class "Default")
      (node (ref "P6") (pin "57") (pinfunction "57_57") (pintype "passive+no_connect"))
    )
    (net (code "99") (name "unconnected-(P6-Pad58)") (class "Default")
      (node (ref "P6") (pin "58") (pinfunction "58_58") (pintype "passive+no_connect"))
    )
    (net (code "100") (name "unconnected-(P6-Pad59)") (class "Default")
      (node (ref "P6") (pin "59") (pinfunction "59_59") (pintype "passive+no_connect"))
    )
    (net (code "101") (name "unconnected-(P6-Pad60)") (class "Default")
      (node (ref "P6") (pin "60") (pinfunction "60_60") (pintype "passive+no_connect"))
    )
    (net (code "102") (name "unconnected-(P7-Pad1)") (class "Default")
      (node (ref "P7") (pin "1") (pinfunction "1_1") (pintype "passive+no_connect"))
    )
    (net (code "103") (name "unconnected-(P7-Pad2)") (class "Default")
      (node (ref "P7") (pin "2") (pinfunction "2_2") (pintype "passive+no_connect"))
    )
    (net (code "104") (name "unconnected-(P7-Pad3)") (class "Default")
      (node (ref "P7") (pin "3") (pinfunction "3_3") (pintype "passive+no_connect"))
    )
    (net (code "105") (name "unconnected-(P7-Pad4)") (class "Default")
      (node (ref "P7") (pin "4") (pinfunction "4_4") (pintype "passive+no_connect"))
    )
    (net (code "106") (name "unconnected-(P7-Pad5)") (class "Default")
      (node (ref "P7") (pin "5") (pinfunction "5_5") (pintype "passive+no_connect"))
    )
    (net (code "107") (name "unconnected-(P7-Pad6)") (class "Default")
      (node (ref "P7") (pin "6") (pinfunction "6_6") (pintype "passive+no_connect"))
    )
    (net (code "108") (name "unconnected-(P7-Pad7)") (class "Default")
      (node (ref "P7") (pin "7") (pinfunction "7_7") (pintype "passive+no_connect"))
    )
    (net (code "109") (name "unconnected-(P7-Pad8)") (class "Default")
      (node (ref "P7") (pin "8") (pinfunction "8_8") (pintype "passive+no_connect"))
    )
    (net (code "110") (name "unconnected-(P7-Pad9)") (class "Default")
      (node (ref "P7") (pin "9") (pinfunction "9_9") (pintype "passive+no_connect"))
    )
    (net (code "111") (name "unconnected-(P7-Pad10)") (class "Default")
      (node (ref "P7") (pin "10") (pinfunction "10_10") (pintype "passive+no_connect"))
    )
    (net (code "112") (name "unconnected-(P7-Pad13)") (class "Default")
      (node (ref "P7") (pin "13") (pinfunction "13_13") (pintype "passive+no_connect"))
    )
    (net (code "113") (name "unconnected-(P7-Pad14)") (class "Default")
      (node (ref "P7") (pin "14") (pinfunction "14_14") (pintype "passive+no_connect"))
    )
    (net (code "114") (name "unconnected-(P7-Pad15)") (class "Default")
      (node (ref "P7") (pin "15") (pinfunction "15_15") (pintype "passive+no_connect"))
    )
    (net (code "115") (name "unconnected-(P7-Pad16)") (class "Default")
      (node (ref "P7") (pin "16") (pinfunction "16_16") (pintype "passive+no_connect"))
    )
    (net (code "116") (name "unconnected-(P7-Pad17)") (class "Default")
      (node (ref "P7") (pin "17") (pinfunction "17_17") (pintype "passive+no_connect"))
    )
    (net (code "117") (name "unconnected-(P7-Pad18)") (class "Default")
      (node (ref "P7") (pin "18") (pinfunction "18_18") (pintype "passive+no_connect"))
    )
    (net (code "118") (name "unconnected-(P7-Pad19)") (class "Default")
      (node (ref "P7") (pin "19") (pinfunction "19_19") (pintype "passive+no_connect"))
    )
    (net (code "119") (name "unconnected-(P7-Pad20)") (class "Default")
      (node (ref "P7") (pin "20") (pinfunction "20_20") (pintype "passive+no_connect"))
    )
    (net (code "120") (name "unconnected-(P7-Pad23)") (class "Default")
      (node (ref "P7") (pin "23") (pinfunction "23_23") (pintype "passive+no_connect"))
    )
    (net (code "121") (name "unconnected-(P7-Pad24)") (class "Default")
      (node (ref "P7") (pin "24") (pinfunction "24_24") (pintype "passive+no_connect"))
    )
    (net (code "122") (name "unconnected-(P7-Pad25)") (class "Default")
      (node (ref "P7") (pin "25") (pinfunction "25_25") (pintype "passive+no_connect"))
    )
    (net (code "123") (name "unconnected-(P7-Pad26)") (class "Default")
      (node (ref "P7") (pin "26") (pinfunction "26_26") (pintype "passive+no_connect"))
    )
    (net (code "124") (name "unconnected-(P7-Pad27)") (class "Default")
      (node (ref "P7") (pin "27") (pinfunction "27_27") (pintype "passive+no_connect"))
    )
    (net (code "125") (name "unconnected-(P7-Pad28)") (class "Default")
      (node (ref "P7") (pin "28") (pinfunction "28_28") (pintype "passive+no_connect"))
    )
    (net (code "126") (name "unconnected-(P7-Pad29)") (class "Default")
      (node (ref "P7") (pin "29") (pinfunction "29_29") (pintype "passive+no_connect"))
    )
    (net (code "127") (name "unconnected-(P7-Pad30)") (class "Default")
      (node (ref "P7") (pin "30") (pinfunction "30_30") (pintype "passive+no_connect"))
    )
    (net (code "128") (name "unconnected-(P7-Pad33)") (class "Default")
      (node (ref "P7") (pin "33") (pinfunction "33_33") (pintype "passive+no_connect"))
    )
    (net (code "129") (name "unconnected-(P7-Pad34)") (class "Default")
      (node (ref "P7") (pin "34") (pinfunction "34_34") (pintype "passive+no_connect"))
    )
    (net (code "130") (name "unconnected-(P7-Pad35)") (class "Default")
      (node (ref "P7") (pin "35") (pinfunction "35_35") (pintype "passive+no_connect"))
    )
    (net (code "131") (name "unconnected-(P7-Pad36)") (class "Default")
      (node (ref "P7") (pin "36") (pinfunction "36_36") (pintype "passive+no_connect"))
    )
    (net (code "132") (name "unconnected-(P7-Pad37)") (class "Default")
      (node (ref "P7") (pin "37") (pinfunction "37_37") (pintype "passive+no_connect"))
    )
    (net (code "133") (name "unconnected-(P7-Pad38)") (class "Default")
      (node (ref "P7") (pin "38") (pinfunction "38_38") (pintype "passive+no_connect"))
    )
    (net (code "134") (name "unconnected-(P7-Pad39)") (class "Default")
      (node (ref "P7") (pin "39") (pinfunction "39_39") (pintype "passive+no_connect"))
    )
    (net (code "135") (name "unconnected-(P7-Pad40)") (class "Default")
      (node (ref "P7") (pin "40") (pinfunction "40_40") (pintype "passive+no_connect"))
    )
    (net (code "136") (name "unconnected-(P7-Pad43)") (class "Default")
      (node (ref "P7") (pin "43") (pinfunction "43_43") (pintype "passive+no_connect"))
    )
    (net (code "137") (name "unconnected-(P7-Pad44)") (class "Default")
      (node (ref "P7") (pin "44") (pinfunction "44_44") (pintype "passive+no_connect"))
    )
    (net (code "138") (name "unconnected-(P7-Pad45)") (class "Default")
      (node (ref "P7") (pin "45") (pinfunction "45_45") (pintype "passive+no_connect"))
    )
    (net (code "139") (name "unconnected-(P7-Pad46)") (class "Default")
      (node (ref "P7") (pin "46") (pinfunction "46_46") (pintype "passive+no_connect"))
    )
    (net (code "140") (name "unconnected-(P7-Pad47)") (class "Default")
      (node (ref "P7") (pin "47") (pinfunction "47_47") (pintype "passive+no_connect"))
    )
    (net (code "141") (name "unconnected-(P7-Pad48)") (class "Default")
      (node (ref "P7") (pin "48") (pinfunction "48_48") (pintype "passive+no_connect"))
    )
    (net (code "142") (name "unconnected-(P7-Pad49)") (class "Default")
      (node (ref "P7") (pin "49") (pinfunction "49_49") (pintype "passive+no_connect"))
    )
    (net (code "143") (name "unconnected-(P7-Pad50)") (class "Default")
      (node (ref "P7") (pin "50") (pinfunction "50_50") (pintype "passive+no_connect"))
    )
    (net (code "144") (name "unconnected-(P7-Pad53)") (class "Default")
      (node (ref "P7") (pin "53") (pinfunction "53_53") (pintype "passive+no_connect"))
    )
    (net (code "145") (name "unconnected-(P7-Pad54)") (class "Default")
      (node (ref "P7") (pin "54") (pinfunction "54_54") (pintype "passive+no_connect"))
    )
    (net (code "146") (name "unconnected-(P7-Pad55)") (class "Default")
      (node (ref "P7") (pin "55") (pinfunction "55_55") (pintype "passive+no_connect"))
    )
    (net (code "147") (name "unconnected-(P7-Pad56)") (class "Default")
      (node (ref "P7") (pin "56") (pinfunction "56_56") (pintype "passive+no_connect"))
    )
    (net (code "148") (name "unconnected-(P7-Pad57)") (class "Default")
      (node (ref "P7") (pin "57") (pinfunction "57_57") (pintype "passive+no_connect"))
    )
    (net (code "149") (name "unconnected-(P7-Pad58)") (class "Default")
      (node (ref "P7") (pin "58") (pinfunction "58_58") (pintype "passive+no_connect"))
    )
    (net (code "150") (name "unconnected-(P7-Pad59)") (class "Default")
      (node (ref "P7") (pin "59") (pinfunction "59_59") (pintype "passive+no_connect"))
    )
    (net (code "151") (name "unconnected-(P7-Pad60)") (class "Default")
      (node (ref "P7") (pin "60") (pinfunction "60_60") (pintype "passive+no_connect"))
    )
    (net (code "152") (name "unconnected-(P8-Pad1)") (class "Default")
      (node (ref "P8") (pin "1") (pinfunction "1_1") (pintype "passive+no_connect"))
    )
    (net (code "153") (name "unconnected-(P8-Pad2)") (class "Default")
      (node (ref "P8") (pin "2") (pinfunction "2_2") (pintype "passive+no_connect"))
    )
    (net (code "154") (name "unconnected-(P8-Pad3)") (class "Default")
      (node (ref "P8") (pin "3") (pinfunction "3_3") (pintype "passive+no_connect"))
    )
    (net (code "155") (name "unconnected-(P8-Pad4)") (class "Default")
      (node (ref "P8") (pin "4") (pinfunction "4_4") (pintype "passive+no_connect"))
    )
    (net (code "156") (name "unconnected-(P8-Pad5)") (class "Default")
      (node (ref "P8") (pin "5") (pinfunction "5_5") (pintype "passive+no_connect"))
    )
    (net (code "157") (name "unconnected-(P8-Pad6)") (class "Default")
      (node (ref "P8") (pin "6") (pinfunction "6_6") (pintype "passive+no_connect"))
    )
    (net (code "158") (name "unconnected-(P8-Pad7)") (class "Default")
      (node (ref "P8") (pin "7") (pinfunction "7_7") (pintype "passive+no_connect"))
    )
    (net (code "159") (name "unconnected-(P8-Pad8)") (class "Default")
      (node (ref "P8") (pin "8") (pinfunction "8_8") (pintype "passive+no_connect"))
    )
    (net (code "160") (name "unconnected-(P8-Pad9)") (class "Default")
      (node (ref "P8") (pin "9") (pinfunction "9_9") (pintype "passive+no_connect"))
    )
    (net (code "161") (name "unconnected-(P8-Pad10)") (class "Default")
      (node (ref "P8") (pin "10") (pinfunction "10_10") (pintype "passive+no_connect"))
    )
    (net (code "162") (name "unconnected-(P8-Pad13)") (class "Default")
      (node (ref "P8") (pin "13") (pinfunction "13_13") (pintype "passive+no_connect"))
    )
    (net (code "163") (name "unconnected-(P8-Pad14)") (class "Default")
      (node (ref "P8") (pin "14") (pinfunction "14_14") (pintype "passive+no_connect"))
    )
    (net (code "164") (name "unconnected-(P8-Pad15)") (class "Default")
      (node (ref "P8") (pin "15") (pinfunction "15_15") (pintype "passive+no_connect"))
    )
    (net (code "165") (name "unconnected-(P8-Pad16)") (class "Default")
      (node (ref "P8") (pin "16") (pinfunction "16_16") (pintype "passive+no_connect"))
    )
    (net (code "166") (name "unconnected-(P8-Pad17)") (class "Default")
      (node (ref "P8") (pin "17") (pinfunction "17_17") (pintype "passive+no_connect"))
    )
    (net (code "167") (name "unconnected-(P8-Pad18)") (class "Default")
      (node (ref "P8") (pin "18") (pinfunction "18_18") (pintype "passive+no_connect"))
    )
    (net (code "168") (name "unconnected-(P8-Pad19)") (class "Default")
      (node (ref "P8") (pin "19") (pinfunction "19_19") (pintype "passive+no_connect"))
    )
    (net (code "169") (name "unconnected-(P8-Pad20)") (class "Default")
      (node (ref "P8") (pin "20") (pinfunction "20_20") (pintype "passive+no_connect"))
    )
    (net (code "170") (name "unconnected-(P8-Pad23)") (class "Default")
      (node (ref "P8") (pin "23") (pinfunction "23_23") (pintype "passive+no_connect"))
    )
    (net (code "171") (name "unconnected-(P8-Pad24)") (class "Default")
      (node (ref "P8") (pin "24") (pinfunction "24_24") (pintype "passive+no_connect"))
    )
    (net (code "172") (name "unconnected-(P8-Pad25)") (class "Default")
      (node (ref "P8") (pin "25") (pinfunction "25_25") (pintype "passive+no_connect"))
    )
    (net (code "173") (name "unconnected-(P8-Pad26)") (class "Default")
      (node (ref "P8") (pin "26") (pinfunction "26_26") (pintype "passive+no_connect"))
    )
    (net (code "174") (name "unconnected-(P8-Pad27)") (class "Default")
      (node (ref "P8") (pin "27") (pinfunction "27_27") (pintype "passive+no_connect"))
    )
    (net (code "175") (name "unconnected-(P8-Pad28)") (class "Default")
      (node (ref "P8") (pin "28") (pinfunction "28_28") (pintype "passive+no_connect"))
    )
    (net (code "176") (name "unconnected-(P8-Pad29)") (class "Default")
      (node (ref "P8") (pin "29") (pinfunction "29_29") (pintype "passive+no_connect"))
    )
    (net (code "177") (name "unconnected-(P8-Pad30)") (class "Default")
      (node (ref "P8") (pin "30") (pinfunction "30_30") (pintype "passive+no_connect"))
    )
    (net (code "178") (name "unconnected-(P8-Pad33)") (class "Default")
      (node (ref "P8") (pin "33") (pinfunction "33_33") (pintype "passive+no_connect"))
    )
    (net (code "179") (name "unconnected-(P8-Pad34)") (class "Default")
      (node (ref "P8") (pin "34") (pinfunction "34_34") (pintype "passive+no_connect"))
    )
    (net (code "180") (name "unconnected-(P8-Pad37)") (class "Default")
      (node (ref "P8") (pin "37") (pinfunction "37_37") (pintype "passive+no_connect"))
    )
    (net (code "181") (name "unconnected-(P8-Pad38)") (class "Default")
      (node (ref "P8") (pin "38") (pinfunction "38_38") (pintype "passive+no_connect"))
    )
    (net (code "182") (name "unconnected-(P8-Pad39)") (class "Default")
      (node (ref "P8") (pin "39") (pinfunction "39_39") (pintype "passive+no_connect"))
    )
    (net (code "183") (name "unconnected-(P8-Pad40)") (class "Default")
      (node (ref "P8") (pin "40") (pinfunction "40_40") (pintype "passive+no_connect"))
    )
    (net (code "184") (name "unconnected-(P8-Pad43)") (class "Default")
      (node (ref "P8") (pin "43") (pinfunction "43_43") (pintype "passive+no_connect"))
    )
    (net (code "185") (name "unconnected-(P8-Pad44)") (class "Default")
      (node (ref "P8") (pin "44") (pinfunction "44_44") (pintype "passive+no_connect"))
    )
    (net (code "186") (name "unconnected-(P8-Pad45)") (class "Default")
      (node (ref "P8") (pin "45") (pinfunction "45_45") (pintype "passive+no_connect"))
    )
    (net (code "187") (name "unconnected-(P8-Pad46)") (class "Default")
      (node (ref "P8") (pin "46") (pinfunction "46_46") (pintype "passive+no_connect"))
    )
    (net (code "188") (name "unconnected-(P8-Pad47)") (class "Default")
      (node (ref "P8") (pin "47") (pinfunction "47_47") (pintype "passive+no_connect"))
    )
    (net (code "189") (name "unconnected-(P8-Pad48)") (class "Default")
      (node (ref "P8") (pin "48") (pinfunction "48_48") (pintype "passive+no_connect"))
    )
    (net (code "190") (name "unconnected-(P8-Pad49)") (class "Default")
      (node (ref "P8") (pin "49") (pinfunction "49_49") (pintype "passive+no_connect"))
    )
    (net (code "191") (name "unconnected-(P8-Pad50)") (class "Default")
      (node (ref "P8") (pin "50") (pinfunction "50_50") (pintype "passive+no_connect"))
    )
    (net (code "192") (name "unconnected-(P8-Pad53)") (class "Default")
      (node (ref "P8") (pin "53") (pinfunction "53_53") (pintype "passive+no_connect"))
    )
    (net (code "193") (name "unconnected-(P8-Pad54)") (class "Default")
      (node (ref "P8") (pin "54") (pinfunction "54_54") (pintype "passive+no_connect"))
    )
    (net (code "194") (name "unconnected-(P8-Pad55)") (class "Default")
      (node (ref "P8") (pin "55") (pinfunction "55_55") (pintype "passive+no_connect"))
    )
    (net (code "195") (name "unconnected-(P8-Pad56)") (class "Default")
      (node (ref "P8") (pin "56") (pinfunction "56_56") (pintype "passive+no_connect"))
    )
    (net (code "196") (name "unconnected-(P8-Pad57)") (class "Default")
      (node (ref "P8") (pin "57") (pinfunction "57_57") (pintype "passive+no_connect"))
    )
    (net (code "197") (name "unconnected-(P8-Pad58)") (class "Default")
      (node (ref "P8") (pin "58") (pinfunction "58_58") (pintype "passive+no_connect"))
    )
    (net (code "198") (name "unconnected-(P8-Pad59)") (class "Default")
      (node (ref "P8") (pin "59") (pinfunction "59_59") (pintype "passive+no_connect"))
    )
    (net (code "199") (name "unconnected-(P8-Pad60)") (class "Default")
      (node (ref "P8") (pin "60") (pinfunction "60_60") (pintype "passive+no_connect"))
    )
  )
)
